# breadboard_rev06_resized.net
KiCad netlist of a schematic drawn in EAGLE
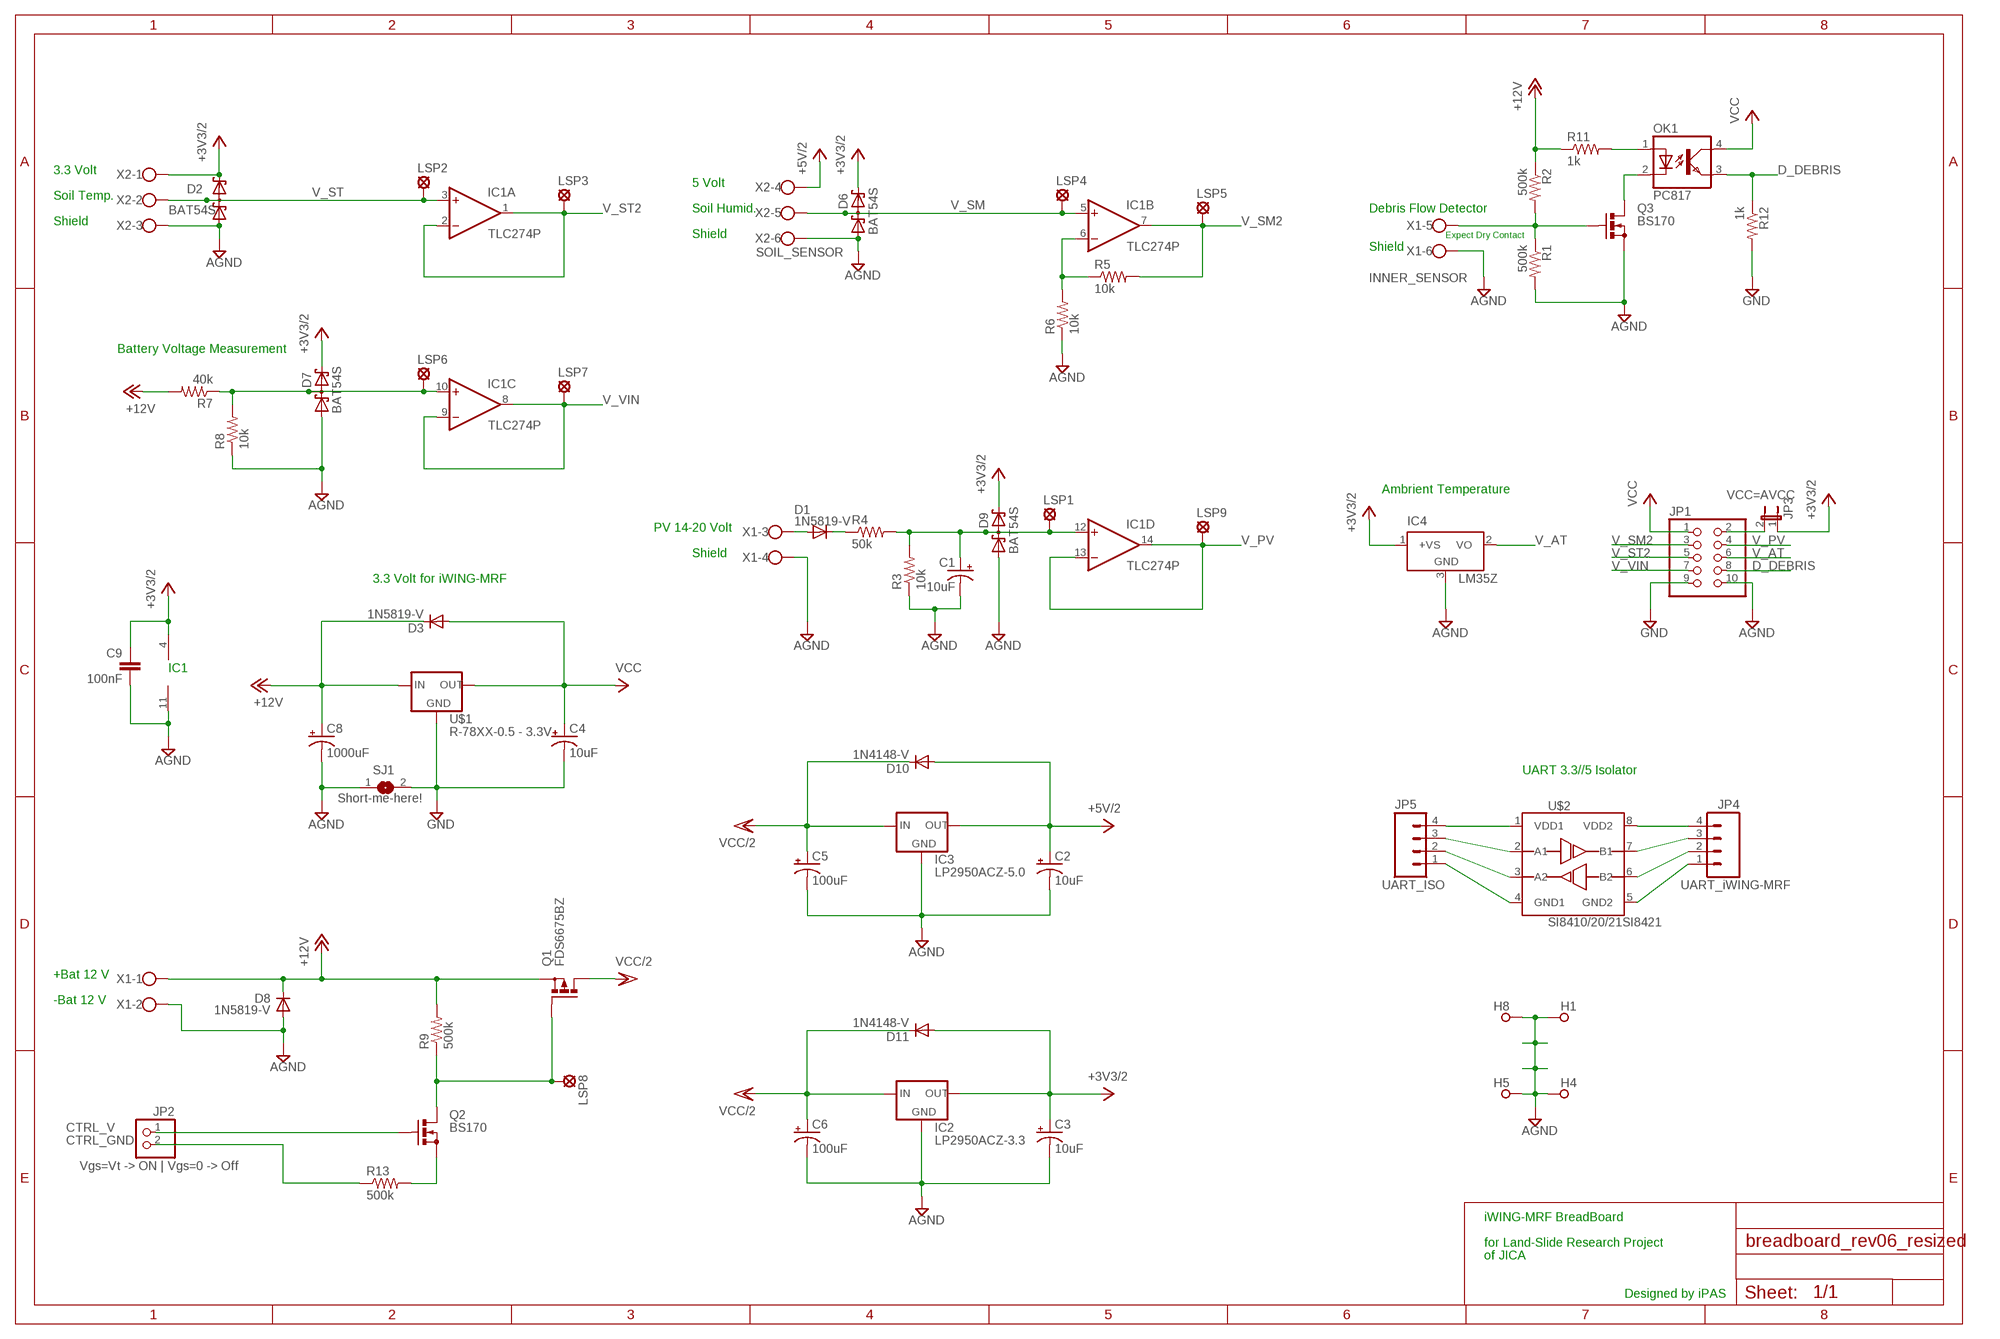
[diagram p0: schematic, sheet 1]

(export (version "E")
  (design (tool "Eeschema 10.0.6"))
  (components
    (comp (ref "C1")
      (value "10uF")
      (footprint "eagle-import:RCL_E2,5-7")
      (libsource (lib "eagle-import") (part "RCL_CPOL-USE2.5-7"))
    )
    (comp (ref "C2")
      (value "10uF")
      (footprint "eagle-import:RCL_E2,5-7")
      (libsource (lib "eagle-import") (part "RCL_CPOL-USE2.5-7"))
    )
    (comp (ref "C3")
      (value "10uF")
      (footprint "eagle-import:RCL_E2,5-7")
      (libsource (lib "eagle-import") (part "RCL_CPOL-USE2.5-7"))
    )
    (comp (ref "C4")
      (value "10uF")
      (footprint "eagle-import:RCL_E2,5-7")
      (libsource (lib "eagle-import") (part "RCL_CPOL-USE2.5-7"))
    )
    (comp (ref "C5")
      (value "100uF")
      (footprint "eagle-import:RCL_E2,5-7")
      (libsource (lib "eagle-import") (part "RCL_CPOL-USE2.5-7"))
    )
    (comp (ref "C6")
      (value "100uF")
      (footprint "eagle-import:RCL_E2,5-7")
      (libsource (lib "eagle-import") (part "RCL_CPOL-USE2.5-7"))
    )
    (comp (ref "C8")
      (value "1000uF")
      (footprint "eagle-import:RCL_E5-13")
      (libsource (lib "eagle-import") (part "RCL_CPOL-USE5-13"))
    )
    (comp (ref "C9")
      (value "100nF")
      (footprint "eagle-import:RCL_C050-025X075")
      (libsource (lib "eagle-import") (part "RCL_C-EU050-025X075"))
    )
    (comp (ref "D1")
      (value "1N5819-V")
      (footprint "eagle-import:DO41-150V")
      (libsource (lib "eagle-import") (part "1N5819-V"))
    )
    (comp (ref "D2")
      (value "BAT54S")
      (footprint "eagle-import:SOT23")
      (libsource (lib "eagle-import") (part "BAT54S"))
    )
    (comp (ref "D3")
      (value "1N5819-V")
      (footprint "eagle-import:DO41-150V")
      (libsource (lib "eagle-import") (part "1N5819-V"))
    )
    (comp (ref "D6")
      (value "BAT54S")
      (footprint "eagle-import:SOT23")
      (libsource (lib "eagle-import") (part "BAT54S"))
    )
    (comp (ref "D7")
      (value "BAT54S")
      (footprint "eagle-import:SOT23")
      (libsource (lib "eagle-import") (part "BAT54S"))
    )
    (comp (ref "D8")
      (value "1N5819-V")
      (footprint "eagle-import:DO41-150V")
      (libsource (lib "eagle-import") (part "1N5819-V"))
    )
    (comp (ref "D9")
      (value "BAT54S")
      (footprint "eagle-import:SOT23")
      (libsource (lib "eagle-import") (part "BAT54S"))
    )
    (comp (ref "D10")
      (value "1N4148-V")
      (footprint "eagle-import:DO35-100V")
      (libsource (lib "eagle-import") (part "1N4148-V"))
    )
    (comp (ref "D11")
      (value "1N4148-V")
      (footprint "eagle-import:DO35-100V")
      (libsource (lib "eagle-import") (part "1N4148-V"))
    )
    (comp (ref "H1")
      (value "SPECIAL_DRILL_0.1560")
      (footprint "eagle-import:PAD_0.1560")
      (libsource (lib "eagle-import") (part "SPECIAL_DRILL_0.1560"))
    )
    (comp (ref "H4")
      (value "SPECIAL_DRILL_0.1560")
      (footprint "eagle-import:PAD_0.1560")
      (libsource (lib "eagle-import") (part "SPECIAL_DRILL_0.1560"))
    )
    (comp (ref "H5")
      (value "SPECIAL_DRILL_0.1560")
      (footprint "eagle-import:PAD_0.1560")
      (libsource (lib "eagle-import") (part "SPECIAL_DRILL_0.1560"))
    )
    (comp (ref "H8")
      (value "SPECIAL_DRILL_0.1560")
      (footprint "eagle-import:PAD_0.1560")
      (libsource (lib "eagle-import") (part "SPECIAL_DRILL_0.1560"))
    )
    (comp (ref "IC1")
      (value "TLC274P")
      (footprint "eagle-import:DIL14")
      (libsource (lib "eagle-import") (part "TLC274P"))
    )
    (comp (ref "IC2")
      (value "LP2950ACZ-3.3")
      (footprint "eagle-import:TO92")
      (libsource (lib "eagle-import") (part "LP2950?ACZ-3.3"))
    )
    (comp (ref "IC3")
      (value "LP2950ACZ-5.0")
      (footprint "eagle-import:TO92")
      (libsource (lib "eagle-import") (part "LP2950?ACZ-5.0"))
    )
    (comp (ref "IC4")
      (value "LM35Z")
      (footprint "eagle-import:TO92")
      (libsource (lib "eagle-import") (part "LM35?Z"))
    )
    (comp (ref "JP1")
      (value "HEADER-2X5")
      (footprint "eagle-import:2X05")
      (libsource (lib "eagle-import") (part "HEADER-2X5"))
    )
    (comp (ref "JP2")
      (value "Vgs=Vt -> ON | Vgs=0 -> Off")
      (footprint "eagle-import:1X02")
      (libsource (lib "eagle-import") (part "PINHD-1X2"))
    )
    (comp (ref "JP3")
      (value "VCC=AVCC")
      (footprint "eagle-import:JUMPER_JP1")
      (libsource (lib "eagle-import") (part "JP1E"))
    )
    (comp (ref "JP4")
      (value "UART_iWING-MRF")
      (footprint "eagle-import:MOLEX-1X4")
      (libsource (lib "eagle-import") (part "M04POLAR"))
    )
    (comp (ref "JP5")
      (value "UART_ISO")
      (footprint "eagle-import:MOLEX-1X4")
      (libsource (lib "eagle-import") (part "M04POLAR"))
    )
    (comp (ref "LSP1")
      (value "LSP13")
      (footprint "eagle-import:LSP13")
      (libsource (lib "eagle-import") (part "LSP13"))
    )
    (comp (ref "LSP2")
      (value "LSP13")
      (footprint "eagle-import:LSP13")
      (libsource (lib "eagle-import") (part "LSP13"))
    )
    (comp (ref "LSP3")
      (value "LSP13")
      (footprint "eagle-import:LSP13")
      (libsource (lib "eagle-import") (part "LSP13"))
    )
    (comp (ref "LSP4")
      (value "LSP13")
      (footprint "eagle-import:LSP13")
      (libsource (lib "eagle-import") (part "LSP13"))
    )
    (comp (ref "LSP5")
      (value "LSP13")
      (footprint "eagle-import:LSP13")
      (libsource (lib "eagle-import") (part "LSP13"))
    )
    (comp (ref "LSP6")
      (value "LSP13")
      (footprint "eagle-import:LSP13")
      (libsource (lib "eagle-import") (part "LSP13"))
    )
    (comp (ref "LSP7")
      (value "LSP13")
      (footprint "eagle-import:LSP13")
      (libsource (lib "eagle-import") (part "LSP13"))
    )
    (comp (ref "LSP8")
      (value "LSP13")
      (footprint "eagle-import:LSP13")
      (libsource (lib "eagle-import") (part "LSP13"))
    )
    (comp (ref "LSP9")
      (value "LSP13")
      (footprint "eagle-import:LSP13")
      (libsource (lib "eagle-import") (part "LSP13"))
    )
    (comp (ref "OK1")
      (value "PC817")
      (footprint "eagle-import:DIL04")
      (fields (field (name "MPN") "PC817X4J000F"))
      (libsource (lib "eagle-import") (part "PC817"))
    )
    (comp (ref "Q1")
      (value "FDS6675BZ")
      (footprint "eagle-import:SO-08")
      (libsource (lib "eagle-import") (part "P-MOSFET-SO8"))
    )
    (comp (ref "Q2")
      (value "BS170")
      (footprint "eagle-import:SOT54E")
      (libsource (lib "eagle-import") (part "BS170"))
    )
    (comp (ref "Q3")
      (value "BS170")
      (footprint "eagle-import:SOT54E")
      (libsource (lib "eagle-import") (part "BS170"))
    )
    (comp (ref "R1")
      (value "500k")
      (footprint "eagle-import:RCL_0204_7")
      (libsource (lib "eagle-import") (part "RCL_R-US_0204/7"))
    )
    (comp (ref "R2")
      (value "500k")
      (footprint "eagle-import:RCL_0204_7")
      (libsource (lib "eagle-import") (part "RCL_R-US_0204/7"))
    )
    (comp (ref "R3")
      (value "10k")
      (footprint "eagle-import:RCL_0204_7")
      (libsource (lib "eagle-import") (part "RCL_R-US_0204/7"))
    )
    (comp (ref "R4")
      (value "50k")
      (footprint "eagle-import:RCL_0204_7")
      (libsource (lib "eagle-import") (part "RCL_R-US_0204/7"))
    )
    (comp (ref "R5")
      (value "10k")
      (footprint "eagle-import:RCL_0204_7")
      (libsource (lib "eagle-import") (part "RCL_R-US_0204/7"))
    )
    (comp (ref "R6")
      (value "10k")
      (footprint "eagle-import:RCL_0204_7")
      (libsource (lib "eagle-import") (part "RCL_R-US_0204/7"))
    )
    (comp (ref "R7")
      (value "40k")
      (footprint "eagle-import:RCL_0204_7")
      (libsource (lib "eagle-import") (part "RCL_R-US_0204/7"))
    )
    (comp (ref "R8")
      (value "10k")
      (footprint "eagle-import:RCL_0204_7")
      (libsource (lib "eagle-import") (part "RCL_R-US_0204/7"))
    )
    (comp (ref "R9")
      (value "500k")
      (footprint "eagle-import:RCL_0204_7")
      (libsource (lib "eagle-import") (part "RCL_R-US_0204/7"))
    )
    (comp (ref "R11")
      (value "1k")
      (footprint "eagle-import:RCL_0204_7")
      (libsource (lib "eagle-import") (part "RCL_R-US_0204/7"))
    )
    (comp (ref "R12")
      (value "1k")
      (footprint "eagle-import:RCL_0204_7")
      (libsource (lib "eagle-import") (part "RCL_R-US_0204/7"))
    )
    (comp (ref "R13")
      (value "500k")
      (footprint "eagle-import:RCL_0204_7")
      (libsource (lib "eagle-import") (part "RCL_R-US_0204/7"))
    )
    (comp (ref "SJ1")
      (value "Short-me-here!")
      (footprint "eagle-import:SJ")
      (libsource (lib "eagle-import") (part "SJ"))
    )
    (comp (ref "U$1")
      (value "R-78XX-0.5 - 3.3V")
      (footprint "eagle-import:SIP3")
      (libsource (lib "eagle-import") (part "R-78XX-0.5"))
    )
    (comp (ref "U$2")
      (value "SI8410/20/21SI8421")
      (footprint "eagle-import:SO-08")
      (libsource (lib "eagle-import") (part "SI8410/20/21SI8421"))
    )
    (comp (ref "X1")
      (value "INNER_SENSOR")
      (footprint "eagle-import:5EHDRC-6P")
      (libsource (lib "eagle-import") (part "5EHDRC-6P"))
    )
    (comp (ref "X2")
      (value "SOIL_SENSOR")
      (footprint "eagle-import:5EHDRC-6P")
      (libsource (lib "eagle-import") (part "5EHDRC-6P"))
    )
  )
  (nets
    (net (code "1") (name "+3V3{slash}2") (class "Default")
      (node (ref "C3") (pin "+") (pinfunction "+_+") (pintype "passive"))
      (node (ref "C9") (pin "1") (pinfunction "1_1") (pintype "passive"))
      (node (ref "D11") (pin "A") (pinfunction "A_A") (pintype "passive"))
      (node (ref "D2") (pin "2") (pinfunction "C2_2") (pintype "passive"))
      (node (ref "D6") (pin "2") (pinfunction "C2_2") (pintype "passive"))
      (node (ref "D7") (pin "2") (pinfunction "C2_2") (pintype "passive"))
      (node (ref "D9") (pin "2") (pinfunction "C2_2") (pintype "passive"))
      (node (ref "IC1") (pin "4") (pinfunction "V+_4") (pintype "power_in"))
      (node (ref "IC2") (pin "1") (pinfunction "OUT_1") (pintype "passive"))
      (node (ref "IC4") (pin "1") (pinfunction "+VS_1") (pintype "input"))
      (node (ref "JP3") (pin "1") (pinfunction "1_1") (pintype "passive"))
      (node (ref "X2") (pin "1") (pinfunction "KL_1") (pintype "passive"))
    )
    (net (code "2") (name "+5V{slash}2") (class "Default")
      (node (ref "C2") (pin "+") (pinfunction "+_+") (pintype "passive"))
      (node (ref "D10") (pin "A") (pinfunction "A_A") (pintype "passive"))
      (node (ref "IC3") (pin "1") (pinfunction "OUT_1") (pintype "passive"))
      (node (ref "X2") (pin "4") (pinfunction "KL_4") (pintype "passive"))
    )
    (net (code "3") (name "+12V") (class "Default")
      (node (ref "C8") (pin "+") (pinfunction "+_+") (pintype "passive"))
      (node (ref "D3") (pin "C") (pinfunction "C_C") (pintype "passive"))
      (node (ref "D8") (pin "C") (pinfunction "C_C") (pintype "passive"))
      (node (ref "Q1") (pin "1") (pinfunction "S_1") (pintype "passive"))
      (node (ref "Q1") (pin "2") (pinfunction "S_2") (pintype "passive"))
      (node (ref "Q1") (pin "3") (pinfunction "S_3") (pintype "passive"))
      (node (ref "R11") (pin "1") (pinfunction "1_1") (pintype "passive"))
      (node (ref "R2") (pin "1") (pinfunction "1_1") (pintype "passive"))
      (node (ref "R7") (pin "2") (pinfunction "2_2") (pintype "passive"))
      (node (ref "R9") (pin "2") (pinfunction "2_2") (pintype "passive"))
      (node (ref "U$1") (pin "1") (pinfunction "IN_1") (pintype "input"))
      (node (ref "X1") (pin "1") (pinfunction "KL_1") (pintype "passive"))
    )
    (net (code "4") (name "/CTRL_GND") (class "Default")
      (node (ref "JP2") (pin "2") (pinfunction "2_2") (pintype "passive"))
      (node (ref "R13") (pin "1") (pinfunction "1_1") (pintype "passive"))
    )
    (net (code "5") (name "/CTRL_V") (class "Default")
      (node (ref "JP2") (pin "1") (pinfunction "1_1") (pintype "passive"))
      (node (ref "Q2") (pin "G") (pinfunction "G_G") (pintype "passive"))
    )
    (net (code "6") (name "/D_DEBRIS") (class "Default")
      (node (ref "JP1") (pin "8") (pinfunction "8_8") (pintype "passive"))
      (node (ref "OK1") (pin "3") (pinfunction "EMIT_3") (pintype "passive"))
      (node (ref "R12") (pin "1") (pinfunction "1_1") (pintype "passive"))
    )
    (net (code "7") (name "/V_AT") (class "Default")
      (node (ref "IC4") (pin "2") (pinfunction "VO_2") (pintype "output"))
      (node (ref "JP1") (pin "6") (pinfunction "6_6") (pintype "passive"))
    )
    (net (code "8") (name "/V_PV") (class "Default")
      (node (ref "IC1") (pin "13") (pinfunction "-IN_13") (pintype "input"))
      (node (ref "IC1") (pin "14") (pinfunction "OUT_14") (pintype "output"))
      (node (ref "JP1") (pin "4") (pinfunction "4_4") (pintype "passive"))
      (node (ref "LSP9") (pin "MP") (pinfunction "MP_MP") (pintype "passive"))
    )
    (net (code "9") (name "/V_SM") (class "Default")
      (node (ref "D6") (pin "3") (pinfunction "C1A2_3") (pintype "passive"))
      (node (ref "IC1") (pin "5") (pinfunction "+IN_5") (pintype "input"))
      (node (ref "LSP4") (pin "MP") (pinfunction "MP_MP") (pintype "passive"))
      (node (ref "X2") (pin "5") (pinfunction "KL_5") (pintype "passive"))
    )
    (net (code "10") (name "/V_SM2") (class "Default")
      (node (ref "IC1") (pin "7") (pinfunction "OUT_7") (pintype "output"))
      (node (ref "JP1") (pin "3") (pinfunction "3_3") (pintype "passive"))
      (node (ref "LSP5") (pin "MP") (pinfunction "MP_MP") (pintype "passive"))
      (node (ref "R5") (pin "2") (pinfunction "2_2") (pintype "passive"))
    )
    (net (code "11") (name "/V_ST") (class "Default")
      (node (ref "D2") (pin "3") (pinfunction "C1A2_3") (pintype "passive"))
      (node (ref "IC1") (pin "3") (pinfunction "+IN_3") (pintype "input"))
      (node (ref "LSP2") (pin "MP") (pinfunction "MP_MP") (pintype "passive"))
      (node (ref "X2") (pin "2") (pinfunction "KL_2") (pintype "passive"))
    )
    (net (code "12") (name "/V_ST2") (class "Default")
      (node (ref "IC1") (pin "1") (pinfunction "OUT_1") (pintype "output"))
      (node (ref "IC1") (pin "2") (pinfunction "-IN_2") (pintype "input"))
      (node (ref "JP1") (pin "5") (pinfunction "5_5") (pintype "passive"))
      (node (ref "LSP3") (pin "MP") (pinfunction "MP_MP") (pintype "passive"))
    )
    (net (code "13") (name "/V_VIN") (class "Default")
      (node (ref "IC1") (pin "8") (pinfunction "OUT_8") (pintype "output"))
      (node (ref "IC1") (pin "9") (pinfunction "-IN_9") (pintype "input"))
      (node (ref "JP1") (pin "7") (pinfunction "7_7") (pintype "passive"))
      (node (ref "LSP7") (pin "MP") (pinfunction "MP_MP") (pintype "passive"))
    )
    (net (code "14") (name "AGND") (class "Default")
      (node (ref "C1") (pin "-") (pinfunction "-_-") (pintype "passive"))
      (node (ref "C2") (pin "-") (pinfunction "-_-") (pintype "passive"))
      (node (ref "C3") (pin "-") (pinfunction "-_-") (pintype "passive"))
      (node (ref "C5") (pin "-") (pinfunction "-_-") (pintype "passive"))
      (node (ref "C6") (pin "-") (pinfunction "-_-") (pintype "passive"))
      (node (ref "C8") (pin "-") (pinfunction "-_-") (pintype "passive"))
      (node (ref "C9") (pin "2") (pinfunction "2_2") (pintype "passive"))
      (node (ref "D2") (pin "1") (pinfunction "A1_1") (pintype "passive"))
      (node (ref "D6") (pin "1") (pinfunction "A1_1") (pintype "passive"))
      (node (ref "D7") (pin "1") (pinfunction "A1_1") (pintype "passive"))
      (node (ref "D8") (pin "A") (pinfunction "A_A") (pintype "passive"))
      (node (ref "D9") (pin "1") (pinfunction "A1_1") (pintype "passive"))
      (node (ref "H1") (pin "1") (pinfunction "1_1") (pintype "passive"))
      (node (ref "H4") (pin "1") (pinfunction "1_1") (pintype "passive"))
      (node (ref "H5") (pin "1") (pinfunction "1_1") (pintype "passive"))
      (node (ref "H8") (pin "1") (pinfunction "1_1") (pintype "passive"))
      (node (ref "IC1") (pin "11") (pinfunction "V-_11") (pintype "power_in"))
      (node (ref "IC2") (pin "2") (pinfunction "GND_2") (pintype "input"))
      (node (ref "IC3") (pin "2") (pinfunction "GND_2") (pintype "input"))
      (node (ref "IC4") (pin "3") (pinfunction "GND_3") (pintype "power_in"))
      (node (ref "JP1") (pin "10") (pinfunction "10_10") (pintype "passive"))
      (node (ref "Q3") (pin "S") (pinfunction "S_S") (pintype "passive"))
      (node (ref "R1") (pin "2") (pinfunction "2_2") (pintype "passive"))
      (node (ref "R3") (pin "1") (pinfunction "1_1") (pintype "passive"))
      (node (ref "R6") (pin "1") (pinfunction "1_1") (pintype "passive"))
      (node (ref "R8") (pin "1") (pinfunction "1_1") (pintype "passive"))
      (node (ref "SJ1") (pin "1") (pinfunction "1_1") (pintype "passive"))
      (node (ref "X1") (pin "2") (pinfunction "KL_2") (pintype "passive"))
      (node (ref "X1") (pin "4") (pinfunction "KL_4") (pintype "passive"))
      (node (ref "X1") (pin "6") (pinfunction "KL_6") (pintype "passive"))
      (node (ref "X2") (pin "3") (pinfunction "KL_3") (pintype "passive"))
      (node (ref "X2") (pin "6") (pinfunction "KL_6") (pintype "passive"))
    )
    (net (code "15") (name "GND") (class "Default")
      (node (ref "C4") (pin "-") (pinfunction "-_-") (pintype "passive"))
      (node (ref "JP1") (pin "9") (pinfunction "9_9") (pintype "passive"))
      (node (ref "R12") (pin "2") (pinfunction "2_2") (pintype "passive"))
      (node (ref "SJ1") (pin "2") (pinfunction "2_2") (pintype "passive"))
      (node (ref "U$1") (pin "2") (pinfunction "GND_2") (pintype "input"))
    )
    (net (code "16") (name "Net-(D1-PadC)") (class "Default")
      (node (ref "D1") (pin "C") (pinfunction "C_C") (pintype "passive"))
      (node (ref "R4") (pin "1") (pinfunction "1_1") (pintype "passive"))
    )
    (net (code "17") (name "Net-(D7-C1A2)") (class "Default")
      (node (ref "D7") (pin "3") (pinfunction "C1A2_3") (pintype "passive"))
      (node (ref "IC1") (pin "10") (pinfunction "+IN_10") (pintype "input"))
      (node (ref "LSP6") (pin "MP") (pinfunction "MP_MP") (pintype "passive"))
      (node (ref "R7") (pin "1") (pinfunction "1_1") (pintype "passive"))
      (node (ref "R8") (pin "2") (pinfunction "2_2") (pintype "passive"))
    )
    (net (code "18") (name "Net-(D9-C1A2)") (class "Default")
      (node (ref "C1") (pin "+") (pinfunction "+_+") (pintype "passive"))
      (node (ref "D9") (pin "3") (pinfunction "C1A2_3") (pintype "passive"))
      (node (ref "IC1") (pin "12") (pinfunction "+IN_12") (pintype "input"))
      (node (ref "LSP1") (pin "MP") (pinfunction "MP_MP") (pintype "passive"))
      (node (ref "R3") (pin "2") (pinfunction "2_2") (pintype "passive"))
      (node (ref "R4") (pin "2") (pinfunction "2_2") (pintype "passive"))
    )
    (net (code "19") (name "Net-(IC1B--IN)") (class "Default")
      (node (ref "IC1") (pin "6") (pinfunction "-IN_6") (pintype "input"))
      (node (ref "R5") (pin "1") (pinfunction "1_1") (pintype "passive"))
      (node (ref "R6") (pin "2") (pinfunction "2_2") (pintype "passive"))
    )
    (net (code "20") (name "Net-(JP1-Pad2)") (class "Default")
      (node (ref "JP1") (pin "2") (pinfunction "2_2") (pintype "passive"))
      (node (ref "JP3") (pin "2") (pinfunction "2_2") (pintype "passive"))
    )
    (net (code "21") (name "Net-(OK1-A)") (class "Default")
      (node (ref "OK1") (pin "1") (pinfunction "A_1") (pintype "passive"))
      (node (ref "R11") (pin "2") (pinfunction "2_2") (pintype "passive"))
    )
    (net (code "22") (name "Net-(OK1-C)") (class "Default")
      (node (ref "OK1") (pin "2") (pinfunction "C_2") (pintype "passive"))
      (node (ref "Q3") (pin "D") (pinfunction "D_D") (pintype "passive"))
    )
    (net (code "23") (name "Net-(Q1-G)") (class "Default")
      (node (ref "LSP8") (pin "MP") (pinfunction "MP_MP") (pintype "passive"))
      (node (ref "Q1") (pin "4") (pinfunction "G_4") (pintype "passive"))
      (node (ref "Q2") (pin "D") (pinfunction "D_D") (pintype "passive"))
      (node (ref "R9") (pin "1") (pinfunction "1_1") (pintype "passive"))
    )
    (net (code "24") (name "Net-(Q2-PadS)") (class "Default")
      (node (ref "Q2") (pin "S") (pinfunction "S_S") (pintype "passive"))
      (node (ref "R13") (pin "2") (pinfunction "2_2") (pintype "passive"))
    )
    (net (code "25") (name "Net-(U$2-A1)") (class "Default")
      (node (ref "JP5") (pin "3") (pinfunction "3_3") (pintype "passive"))
      (node (ref "U$2") (pin "2") (pinfunction "A1_2") (pintype "input"))
    )
    (net (code "26") (name "Net-(U$2-A2)") (class "Default")
      (node (ref "JP5") (pin "2") (pinfunction "2_2") (pintype "passive"))
      (node (ref "U$2") (pin "3") (pinfunction "A2_3") (pintype "output"))
    )
    (net (code "27") (name "Net-(U$2-B1)") (class "Default")
      (node (ref "JP4") (pin "3") (pinfunction "3_3") (pintype "passive"))
      (node (ref "U$2") (pin "7") (pinfunction "B1_7") (pintype "output"))
    )
    (net (code "28") (name "Net-(U$2-B2)") (class "Default")
      (node (ref "JP4") (pin "2") (pinfunction "2_2") (pintype "passive"))
      (node (ref "U$2") (pin "6") (pinfunction "B2_6") (pintype "input"))
    )
    (net (code "29") (name "Net-(U$2-GND1)") (class "Default")
      (node (ref "JP5") (pin "1") (pinfunction "1_1") (pintype "passive"))
      (node (ref "U$2") (pin "4") (pinfunction "GND1_4") (pintype "power_in"))
    )
    (net (code "30") (name "Net-(U$2-GND2)") (class "Default")
      (node (ref "JP4") (pin "1") (pinfunction "1_1") (pintype "passive"))
      (node (ref "U$2") (pin "5") (pinfunction "GND2_5") (pintype "power_in"))
    )
    (net (code "31") (name "Net-(U$2-VDD1)") (class "Default")
      (node (ref "JP5") (pin "4") (pinfunction "4_4") (pintype "passive"))
      (node (ref "U$2") (pin "1") (pinfunction "VDD1_1") (pintype "power_in"))
    )
    (net (code "32") (name "Net-(U$2-VDD2)") (class "Default")
      (node (ref "JP4") (pin "4") (pinfunction "4_4") (pintype "passive"))
      (node (ref "U$2") (pin "8") (pinfunction "VDD2_8") (pintype "power_in"))
    )
    (net (code "33") (name "Net-(X1C-KL)") (class "Default")
      (node (ref "D1") (pin "A") (pinfunction "A_A") (pintype "passive"))
      (node (ref "X1") (pin "3") (pinfunction "KL_3") (pintype "passive"))
    )
    (net (code "34") (name "Net-(X1E-KL)") (class "Default")
      (node (ref "Q3") (pin "G") (pinfunction "G_G") (pintype "passive"))
      (node (ref "R1") (pin "1") (pinfunction "1_1") (pintype "passive"))
      (node (ref "R2") (pin "2") (pinfunction "2_2") (pintype "passive"))
      (node (ref "X1") (pin "5") (pinfunction "KL_5") (pintype "passive"))
    )
    (net (code "35") (name "VCC") (class "Default")
      (node (ref "C4") (pin "+") (pinfunction "+_+") (pintype "passive"))
      (node (ref "D3") (pin "A") (pinfunction "A_A") (pintype "passive"))
      (node (ref "JP1") (pin "1") (pinfunction "1_1") (pintype "passive"))
      (node (ref "OK1") (pin "4") (pinfunction "COL_4") (pintype "passive"))
      (node (ref "U$1") (pin "3") (pinfunction "OUT_3") (pintype "passive"))
    )
    (net (code "36") (name "VCC{slash}2") (class "Default")
      (node (ref "C5") (pin "+") (pinfunction "+_+") (pintype "passive"))
      (node (ref "C6") (pin "+") (pinfunction "+_+") (pintype "passive"))
      (node (ref "D10") (pin "C") (pinfunction "C_C") (pintype "passive"))
      (node (ref "D11") (pin "C") (pinfunction "C_C") (pintype "passive"))
      (node (ref "IC2") (pin "3") (pinfunction "IN_3") (pintype "input"))
      (node (ref "IC3") (pin "3") (pinfunction "IN_3") (pintype "input"))
      (node (ref "Q1") (pin "5") (pinfunction "D_5") (pintype "passive"))
      (node (ref "Q1") (pin "6") (pinfunction "D_6") (pintype "passive"))
      (node (ref "Q1") (pin "7") (pinfunction "D_7") (pintype "passive"))
      (node (ref "Q1") (pin "8") (pinfunction "D_8") (pintype "passive"))
    )
  )
)
